# Calculator_Sch.net
KiCad netlist of a schematic drawn in Altium Designer
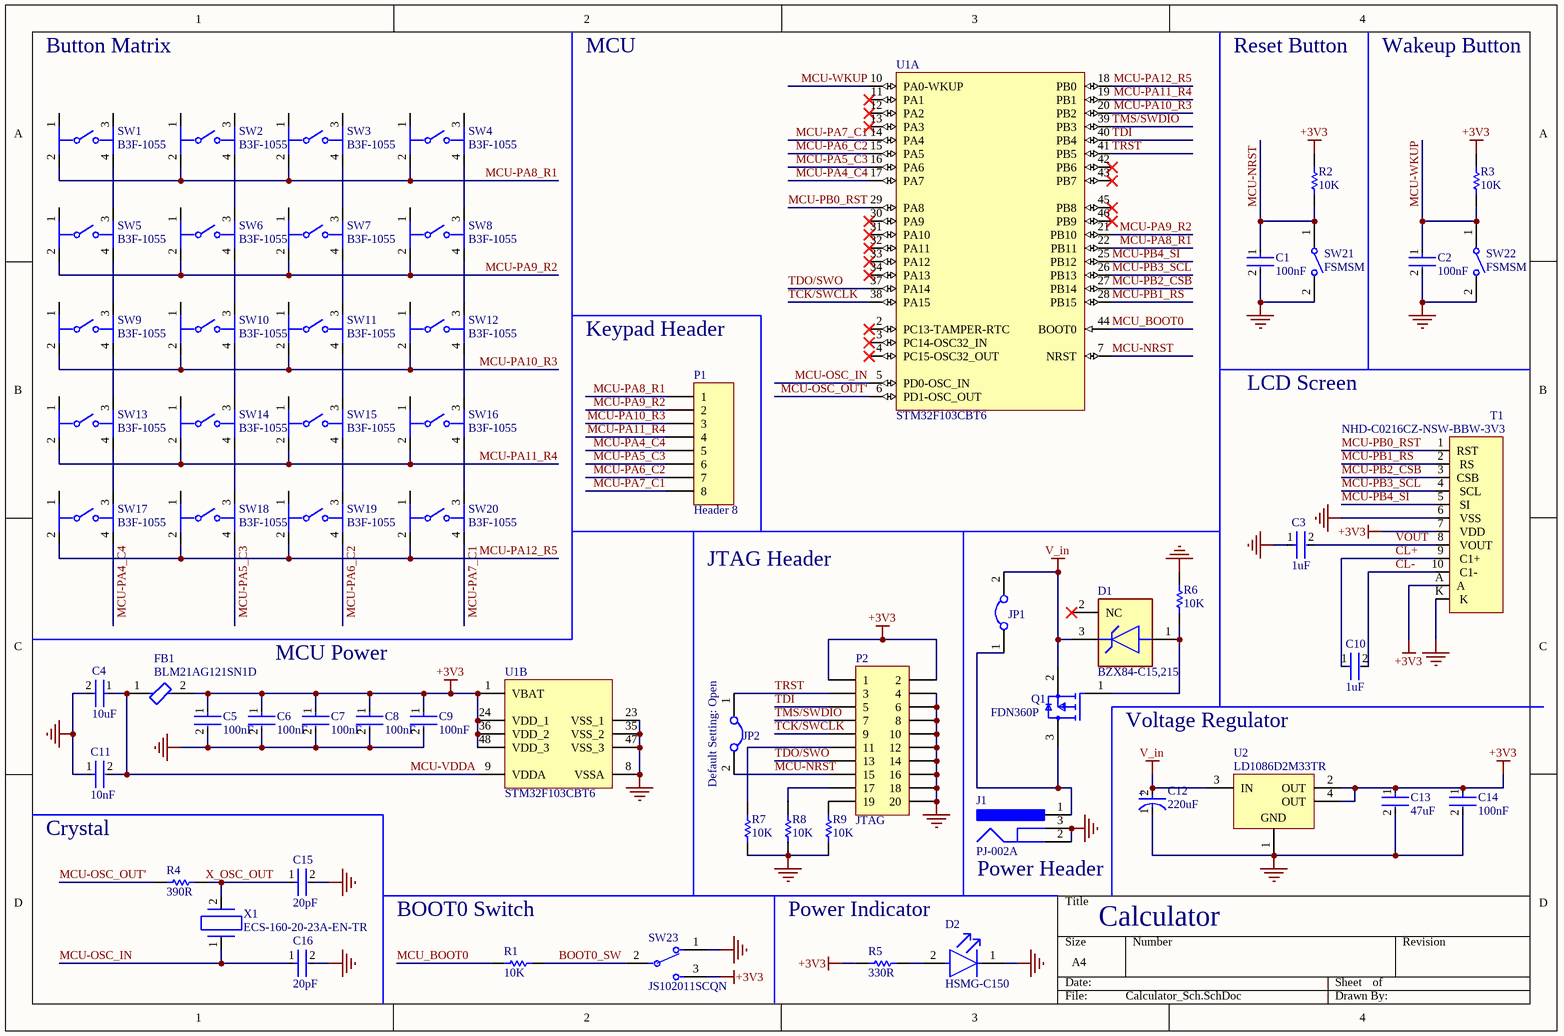
[diagram p0: Calculator_Sch.SchDoc]

(export (version "E")
  (design (tool "Eeschema 10.0.6"))
  (components
    (comp (ref "C1")
      (value "100nF")
      (footprint "FP-C1206C-EB-MFG")
      (description "CAP CER 0.1UF 16V 10% X7R 1206")
      (fields (field (name "MANUFACTURER PART NUMBER") "C1206C104K4RACTU") (field (name "TOLERANCE") "0.1"))
      (libsource (lib "Altium Content Vault") (part "b4654b650e69147ec39a6b967a45e02"))
    )
    (comp (ref "C2")
      (value "100nF")
      (footprint "FP-C1206C-EB-MFG")
      (description "CAP CER 0.1UF 16V 10% X7R 1206")
      (fields (field (name "MANUFACTURER PART NUMBER") "C1206C104K4RACTU") (field (name "TOLERANCE") "0.1"))
      (libsource (lib "Altium Content Vault") (part "b4654b650e69147ec39a6b967a45e02"))
    )
    (comp (ref "C3")
      (value "1uF")
      (footprint "FP-1206-L_3_2_0_2-W_1_6_0-IPC_C")
      (description "General Purpose Ceramic Capacitor, 1206, 1uF, 20%, X7R, 15%, 16V")
      (fields (field (name "TOLERANCE") "20%"))
      (libsource (lib "Altium Content Vault") (part "b4654b650e69147ec39a6b967a45e02"))
    )
    (comp (ref "C4")
      (value "10uF")
      (footprint "FP-1206-L_3_2_0_2-W_1_6_0-IPC_B")
      (description "General Purpose Ceramic Capacitor, 1206, 10uF, 10%, X5R, 15%, 16V")
      (fields (field (name "TOLERANCE") "10%") (field (name "VOLTAGE") "16V"))
      (libsource (lib "Altium Content Vault") (part "02cd4be3c70576c341d710602a673aa"))
    )
    (comp (ref "C5")
      (value "100nF")
      (footprint "FP-C1206C-EB-MFG")
      (description "CAP CER 0.1UF 16V 10% X7R 1206")
      (fields (field (name "MANUFACTURER PART NUMBER") "C1206C104K4RACTU") (field (name "TOLERANCE") "0.1"))
      (libsource (lib "Altium Content Vault") (part "b4654b650e69147ec39a6b967a45e02"))
    )
    (comp (ref "C6")
      (value "100nF")
      (footprint "FP-C1206C-EB-MFG")
      (description "CAP CER 0.1UF 16V 10% X7R 1206")
      (fields (field (name "MANUFACTURER PART NUMBER") "C1206C104K4RACTU") (field (name "TOLERANCE") "0.1"))
      (libsource (lib "Altium Content Vault") (part "b4654b650e69147ec39a6b967a45e02"))
    )
    (comp (ref "C7")
      (value "100nF")
      (footprint "FP-C1206C-EB-MFG")
      (description "CAP CER 0.1UF 16V 10% X7R 1206")
      (fields (field (name "MANUFACTURER PART NUMBER") "C1206C104K4RACTU") (field (name "TOLERANCE") "0.1"))
      (libsource (lib "Altium Content Vault") (part "b4654b650e69147ec39a6b967a45e02"))
    )
    (comp (ref "C8")
      (value "100nF")
      (footprint "FP-C1206C-EB-MFG")
      (description "CAP CER 0.1UF 16V 10% X7R 1206")
      (fields (field (name "MANUFACTURER PART NUMBER") "C1206C104K4RACTU") (field (name "TOLERANCE") "0.1"))
      (libsource (lib "Altium Content Vault") (part "b4654b650e69147ec39a6b967a45e02"))
    )
    (comp (ref "C9")
      (value "100nF")
      (footprint "FP-C1206C-EB-MFG")
      (description "CAP CER 0.1UF 16V 10% X7R 1206")
      (fields (field (name "MANUFACTURER PART NUMBER") "C1206C104K4RACTU") (field (name "TOLERANCE") "0.1"))
      (libsource (lib "Altium Content Vault") (part "b4654b650e69147ec39a6b967a45e02"))
    )
    (comp (ref "C10")
      (value "1uF")
      (footprint "FP-1206-L_3_2_0_2-W_1_6_0-IPC_C")
      (description "General Purpose Ceramic Capacitor, 1206, 1uF, 20%, X7R, 15%, 16V")
      (fields (field (name "TOLERANCE") "20%"))
      (libsource (lib "Altium Content Vault") (part "b4654b650e69147ec39a6b967a45e02"))
    )
    (comp (ref "C11")
      (value "10nF")
      (footprint "FP-C1206C-EB-MFG")
      (description "CAP CER 10000PF 200V X7R 1206")
      (fields
        (field (name "OCTOPART") "https://octopart.com/c1206c103k2ractu-kemet-2299149")
        (field (name "MANUFACTURER") "KEMET")
      )
      (libsource (lib "Altium Content Vault") (part "b4654b650e69147ec39a6b967a45e02"))
    )
    (comp (ref "C12")
      (value "220uF")
      (footprint "FP-TAJE-MFG")
      (description "220uF 16V  ±20% 500mΩ 2917  SMD Tantalum Capacitor")
      (fields (field (name "TOLERANCE") "20%"))
      (libsource (lib "Altium Content Vault") (part "203bc49f2ac43e59fd269a8c329ed05"))
    )
    (comp (ref "C13")
      (value "47uF")
      (footprint "FP-C3216-160-0_2-MFG")
      (description "Multilayer Ceramic Capacitors 47uF ±20% 16V X5R SMD 1206")
      (fields (field (name "TOLERANCE") "20%"))
      (libsource (lib "Altium Content Vault") (part "11868f565c42a9108669ba33697ecf6"))
    )
    (comp (ref "C14")
      (value "100nF")
      (footprint "FP-C1206C-EB-MFG")
      (description "CAP CER 0.1UF 16V 10% X7R 1206")
      (fields (field (name "MANUFACTURER PART NUMBER") "C1206C104K4RACTU") (field (name "TOLERANCE") "0.1"))
      (libsource (lib "Altium Content Vault") (part "b4654b650e69147ec39a6b967a45e02"))
    )
    (comp (ref "C15")
      (value "20pF")
      (footprint "FP-C1206C-EB-MFG")
      (description "1206 C 20pF Ceramic Multilayer Capacitor; 50 VDC; +125degC; C0G Dielec; +/-5%")
      (fields (field (name "TOLERANCE") "0.05") (field (name "MANUFACTURER") "KEMET"))
      (libsource (lib "Altium Content Vault") (part "b4654b650e69147ec39a6b967a45e02"))
    )
    (comp (ref "C16")
      (value "20pF")
      (footprint "FP-C1206C-EB-MFG")
      (description "1206 C 20pF Ceramic Multilayer Capacitor; 50 VDC; +125degC; C0G Dielec; +/-5%")
      (fields (field (name "TOLERANCE") "0.05") (field (name "MANUFACTURER") "KEMET"))
      (libsource (lib "Altium Content Vault") (part "b4654b650e69147ec39a6b967a45e02"))
    )
    (comp (ref "D1")
      (value "BZX84-C15,215")
      (footprint "FP-SOT23-IPC_C")
      (description "DIODE ZENER 15V 250MW TO236AB")
      (libsource (lib "Altium Content Vault") (part "42c7eef1d4f2b235b8dd031160b28fd"))
    )
    (comp (ref "D2")
      (value "HSMG-C150")
      (footprint "FP-HSMG-C150-MFG")
      (description "Surface Mount Chip LEDs")
      (fields (field (name "MANUFACTURER") "Broadcom"))
      (libsource (lib "Altium Content Vault") (part "8706943c75ba83719d021d2fdc84c58"))
    )
    (comp (ref "FB1")
      (value "BLM21AG121SN1D")
      (footprint "FP-BLM21-0_2-t0_85-e0_5-IPC_A")
      (description "FERRITE BEAD 120 OHM 0805 1LN")
      (fields (field (name "TOLERANCE") "25%"))
      (libsource (lib "Altium Content Vault") (part "5f30dd21d616792df468990f7003faa"))
    )
    (comp (ref "J1")
      (value "PJ-002A")
      (footprint "CUI-PJ-002A_V")
      (fields (field (name "MANUFACTURER") "CUIInc."))
      (libsource (lib "Altium Content Vault") (part "JACK-2CD3-RN_B"))
    )
    (comp (ref "JP1")
      (value "Jumper")
      (footprint "Jumper Small - 2.54 - GRAY")
      (libsource (lib "My Library") (part "Jumper"))
    )
    (comp (ref "JP2")
      (value "Jumper")
      (footprint "Jumper Small - 2.54 - GRAY")
      (libsource (lib "My Library") (part "Jumper"))
    )
    (comp (ref "P1")
      (value "Header 8")
      (footprint "HDR1X8")
      (description "Header, 8-Pin")
      (fields (field (name "PUBLISHER") "Altium Limited"))
      (libsource (lib "Miscellaneous Connectors") (part "Header 8"))
    )
    (comp (ref "P2")
      (value "JTAG")
      (footprint "HDR2X10")
      (description "Header, 10-Pin, Dual row")
      (fields (field (name "PUBLISHER") "Altium Limited"))
      (libsource (lib "Miscellaneous Connectors") (part "Header 10X2"))
    )
    (comp (ref "Q1")
      (value "FDN360P")
      (footprint "FP-527AG-IPC_B")
      (description "MOSFET P-CH 30V 2A SSOT3")
      (libsource (lib "Altium Content Vault") (part "d96140c8e79ef71348df71fb49a9466"))
    )
    (comp (ref "R1")
      (value "10K")
      (footprint "RESC3116X65X40ML10T20")
      (description "Chip Resistor, 10 KOhm, +/- 1%, 0.25 W, -55 to 155 degC, 1206 (3216 Metric), RoHS, Tape and Reel")
      (fields (field (name "TOLERANCE") "1%") (field (name "MANUFACTURER") "Yageo"))
      (libsource (lib "Altium Content Vault") (part "RES-2"))
    )
    (comp (ref "R2")
      (value "10K")
      (footprint "RESC3116X65X40ML10T20")
      (description "Chip Resistor, 10 KOhm, +/- 1%, 0.25 W, -55 to 155 degC, 1206 (3216 Metric), RoHS, Tape and Reel")
      (fields (field (name "TOLERANCE") "1%") (field (name "MANUFACTURER") "Yageo"))
      (libsource (lib "Altium Content Vault") (part "RES-2"))
    )
    (comp (ref "R3")
      (value "10K")
      (footprint "RESC3116X65X40ML10T20")
      (description "Chip Resistor, 10 KOhm, +/- 1%, 0.25 W, -55 to 155 degC, 1206 (3216 Metric), RoHS, Tape and Reel")
      (fields (field (name "TOLERANCE") "1%") (field (name "MANUFACTURER") "Yageo"))
      (libsource (lib "Altium Content Vault") (part "RES-2"))
    )
    (comp (ref "R4")
      (value "390R")
      (footprint "RESC3216X60X45NL10T20")
      (fields (field (name "MANUFACTURER") "Vishay Dale") (field (name "PART NUMBER") "CRCW1206390RJNEA"))
      (libsource (lib "Altium Content Vault") (part "RES"))
    )
    (comp (ref "R5")
      (value "330R")
      (footprint "RESC3116X65X40LL10T20")
      (description "Chip Resistor, 330 Ohm, +/- 1%, 250 mW, -55 to 155 degC, 1206 (3216 Metric), RoHS, Tape and Reel")
      (fields (field (name "MANUFACTURER") "Yageo") (field (name "TOLERANCE") "1%"))
      (libsource (lib "Altium Content Vault") (part "RES-2"))
    )
    (comp (ref "R6")
      (value "10K")
      (footprint "RESC3116X65X40ML10T20")
      (description "Chip Resistor, 10 KOhm, +/- 1%, 0.25 W, -55 to 155 degC, 1206 (3216 Metric), RoHS, Tape and Reel")
      (fields (field (name "TOLERANCE") "1%") (field (name "MANUFACTURER") "Yageo"))
      (libsource (lib "Altium Content Vault") (part "RES-2"))
    )
    (comp (ref "R7")
      (value "10K")
      (footprint "RESC3116X65X40ML10T20")
      (description "Chip Resistor, 10 KOhm, +/- 1%, 0.25 W, -55 to 155 degC, 1206 (3216 Metric), RoHS, Tape and Reel")
      (fields (field (name "TOLERANCE") "1%") (field (name "MANUFACTURER") "Yageo"))
      (libsource (lib "Altium Content Vault") (part "RES-2"))
    )
    (comp (ref "R8")
      (value "10K")
      (footprint "RESC3116X65X40ML10T20")
      (description "Chip Resistor, 10 KOhm, +/- 1%, 0.25 W, -55 to 155 degC, 1206 (3216 Metric), RoHS, Tape and Reel")
      (fields (field (name "TOLERANCE") "1%") (field (name "MANUFACTURER") "Yageo"))
      (libsource (lib "Altium Content Vault") (part "RES-2"))
    )
    (comp (ref "R9")
      (value "10K")
      (footprint "RESC3116X65X40ML10T20")
      (description "Chip Resistor, 10 KOhm, +/- 1%, 0.25 W, -55 to 155 degC, 1206 (3216 Metric), RoHS, Tape and Reel")
      (fields (field (name "TOLERANCE") "1%") (field (name "MANUFACTURER") "Yageo"))
      (libsource (lib "Altium Content Vault") (part "RES-2"))
    )
    (comp (ref "SW1")
      (value "B3F-1055")
      (footprint "FP-B3F-1055-MFG")
      (description "SWITCH TACTILE SPST-NO 0.05A 24V")
      (libsource (lib "Altium Content Vault") (part "b8895f3f4cefb76e1819d2863dba89b"))
    )
    (comp (ref "SW2")
      (value "B3F-1055")
      (footprint "FP-B3F-1055-MFG")
      (description "SWITCH TACTILE SPST-NO 0.05A 24V")
      (libsource (lib "Altium Content Vault") (part "b8895f3f4cefb76e1819d2863dba89b"))
    )
    (comp (ref "SW3")
      (value "B3F-1055")
      (footprint "FP-B3F-1055-MFG")
      (description "SWITCH TACTILE SPST-NO 0.05A 24V")
      (libsource (lib "Altium Content Vault") (part "b8895f3f4cefb76e1819d2863dba89b"))
    )
    (comp (ref "SW4")
      (value "B3F-1055")
      (footprint "FP-B3F-1055-MFG")
      (description "SWITCH TACTILE SPST-NO 0.05A 24V")
      (libsource (lib "Altium Content Vault") (part "b8895f3f4cefb76e1819d2863dba89b"))
    )
    (comp (ref "SW5")
      (value "B3F-1055")
      (footprint "FP-B3F-1055-MFG")
      (description "SWITCH TACTILE SPST-NO 0.05A 24V")
      (libsource (lib "Altium Content Vault") (part "b8895f3f4cefb76e1819d2863dba89b"))
    )
    (comp (ref "SW6")
      (value "B3F-1055")
      (footprint "FP-B3F-1055-MFG")
      (description "SWITCH TACTILE SPST-NO 0.05A 24V")
      (libsource (lib "Altium Content Vault") (part "b8895f3f4cefb76e1819d2863dba89b"))
    )
    (comp (ref "SW7")
      (value "B3F-1055")
      (footprint "FP-B3F-1055-MFG")
      (description "SWITCH TACTILE SPST-NO 0.05A 24V")
      (libsource (lib "Altium Content Vault") (part "b8895f3f4cefb76e1819d2863dba89b"))
    )
    (comp (ref "SW8")
      (value "B3F-1055")
      (footprint "FP-B3F-1055-MFG")
      (description "SWITCH TACTILE SPST-NO 0.05A 24V")
      (libsource (lib "Altium Content Vault") (part "b8895f3f4cefb76e1819d2863dba89b"))
    )
    (comp (ref "SW9")
      (value "B3F-1055")
      (footprint "FP-B3F-1055-MFG")
      (description "SWITCH TACTILE SPST-NO 0.05A 24V")
      (libsource (lib "Altium Content Vault") (part "b8895f3f4cefb76e1819d2863dba89b"))
    )
    (comp (ref "SW10")
      (value "B3F-1055")
      (footprint "FP-B3F-1055-MFG")
      (description "SWITCH TACTILE SPST-NO 0.05A 24V")
      (libsource (lib "Altium Content Vault") (part "b8895f3f4cefb76e1819d2863dba89b"))
    )
    (comp (ref "SW11")
      (value "B3F-1055")
      (footprint "FP-B3F-1055-MFG")
      (description "SWITCH TACTILE SPST-NO 0.05A 24V")
      (libsource (lib "Altium Content Vault") (part "b8895f3f4cefb76e1819d2863dba89b"))
    )
    (comp (ref "SW12")
      (value "B3F-1055")
      (footprint "FP-B3F-1055-MFG")
      (description "SWITCH TACTILE SPST-NO 0.05A 24V")
      (libsource (lib "Altium Content Vault") (part "b8895f3f4cefb76e1819d2863dba89b"))
    )
    (comp (ref "SW13")
      (value "B3F-1055")
      (footprint "FP-B3F-1055-MFG")
      (description "SWITCH TACTILE SPST-NO 0.05A 24V")
      (libsource (lib "Altium Content Vault") (part "b8895f3f4cefb76e1819d2863dba89b"))
    )
    (comp (ref "SW14")
      (value "B3F-1055")
      (footprint "FP-B3F-1055-MFG")
      (description "SWITCH TACTILE SPST-NO 0.05A 24V")
      (libsource (lib "Altium Content Vault") (part "b8895f3f4cefb76e1819d2863dba89b"))
    )
    (comp (ref "SW15")
      (value "B3F-1055")
      (footprint "FP-B3F-1055-MFG")
      (description "SWITCH TACTILE SPST-NO 0.05A 24V")
      (libsource (lib "Altium Content Vault") (part "b8895f3f4cefb76e1819d2863dba89b"))
    )
    (comp (ref "SW16")
      (value "B3F-1055")
      (footprint "FP-B3F-1055-MFG")
      (description "SWITCH TACTILE SPST-NO 0.05A 24V")
      (libsource (lib "Altium Content Vault") (part "b8895f3f4cefb76e1819d2863dba89b"))
    )
    (comp (ref "SW17")
      (value "B3F-1055")
      (footprint "FP-B3F-1055-MFG")
      (description "SWITCH TACTILE SPST-NO 0.05A 24V")
      (libsource (lib "Altium Content Vault") (part "b8895f3f4cefb76e1819d2863dba89b"))
    )
    (comp (ref "SW18")
      (value "B3F-1055")
      (footprint "FP-B3F-1055-MFG")
      (description "SWITCH TACTILE SPST-NO 0.05A 24V")
      (libsource (lib "Altium Content Vault") (part "b8895f3f4cefb76e1819d2863dba89b"))
    )
    (comp (ref "SW19")
      (value "B3F-1055")
      (footprint "FP-B3F-1055-MFG")
      (description "SWITCH TACTILE SPST-NO 0.05A 24V")
      (libsource (lib "Altium Content Vault") (part "b8895f3f4cefb76e1819d2863dba89b"))
    )
    (comp (ref "SW20")
      (value "B3F-1055")
      (footprint "FP-B3F-1055-MFG")
      (description "SWITCH TACTILE SPST-NO 0.05A 24V")
      (libsource (lib "Altium Content Vault") (part "b8895f3f4cefb76e1819d2863dba89b"))
    )
    (comp (ref "SW21")
      (value "FSMSM")
      (footprint "TECO-FSMSM-2_V")
      (description "FSMSM Push Button Switch, 50 mA, -35 to 85 degC, 2-Pin SMD, RoHS, Bulk")
      (fields (field (name "MANUFACTURER") "TE Connectivity"))
      (libsource (lib "Altium Content Vault") (part "SW-SPST-2_C"))
    )
    (comp (ref "SW22")
      (value "FSMSM")
      (footprint "TECO-FSMSM-2_V")
      (description "FSMSM Push Button Switch, 50 mA, -35 to 85 degC, 2-Pin SMD, RoHS, Bulk")
      (fields (field (name "MANUFACTURER") "TE Connectivity"))
      (libsource (lib "Altium Content Vault") (part "SW-SPST-2_C"))
    )
    (comp (ref "SW23")
      (value "JS102011SCQN")
      (footprint "FP-JS102011SCQN-MFG")
      (description "SWITCH SLIDE SPDT 300MA 6V")
      (libsource (lib "Altium Content Vault") (part "39e195cbbadc85d1df0d7eb6847d379"))
    )
    (comp (ref "T1")
      (value "NHD-C0216CZ-NSW-BBW-3V3")
      (footprint "NHD-C0216CZ-NSW-BBW-3V3")
      (description "LCD MOD 32DIG 16X2 TRANSMISV WHT")
      (libsource (lib "Calculator_SchLib") (part "NHD-C0216CZ-NSW-BBW-3V3"))
    )
    (comp (ref "U1")
      (value "STM32F103CBT6")
      (footprint "STM-LQFP48_L")
      (libsource (lib "Altium Content Vault") (part "MC-ARM-STM32F103X8_B-SQ48"))
    )
    (comp (ref "U2")
      (value "LD1086D2M33TR")
      (footprint "D2PAK_A_L")
      (description "1.5A, Low Drop Positive Voltage Regulator, 3.3V, 4-Pin D2PAK/A, Tape and Reel")
      (libsource (lib "Altium Content Vault") (part "PM-REG-LD1085-SOT4"))
    )
    (comp (ref "X1")
      (value "ECS-160-20-23A-EN-TR")
      (footprint "ECX-64AEN/64CEN")
      (description "CRYSTAL 16.0000MHZ 20PF SMD")
      (libsource (lib "Calculator_SchLib") (part "ECS-160-20-23A-EN-TR"))
    )
  )
  (nets
    (net (code "1") (name "+3V3") (class "Default")
      (node (ref "C13") (pin "1") (pinfunction "1_1") (pintype "passive"))
      (node (ref "C14") (pin "1") (pinfunction "1_1") (pintype "passive"))
      (node (ref "C5") (pin "1") (pinfunction "1_1") (pintype "passive"))
      (node (ref "C6") (pin "1") (pinfunction "1_1") (pintype "passive"))
      (node (ref "C7") (pin "1") (pinfunction "1_1") (pintype "passive"))
      (node (ref "C8") (pin "1") (pinfunction "1_1") (pintype "passive"))
      (node (ref "C9") (pin "1") (pinfunction "1_1") (pintype "passive"))
      (node (ref "FB1") (pin "2") (pinfunction "2_2") (pintype "passive"))
      (node (ref "P2") (pin "1") (pinfunction "1_1") (pintype "passive"))
      (node (ref "P2") (pin "2") (pinfunction "2_2") (pintype "passive"))
      (node (ref "R2") (pin "2") (pinfunction "2_2") (pintype "passive"))
      (node (ref "R3") (pin "2") (pinfunction "2_2") (pintype "passive"))
      (node (ref "R5") (pin "1") (pinfunction "1_1") (pintype "passive"))
      (node (ref "SW23") (pin "3") (pinfunction "3_3") (pintype "passive"))
      (node (ref "T1") (pin "7") (pinfunction "_VDD_7") (pintype "passive"))
      (node (ref "T1") (pin "A") (pinfunction "A_A") (pintype "passive"))
      (node (ref "U1") (pin "1") (pinfunction "VBAT_1") (pintype "power_in"))
      (node (ref "U1") (pin "24") (pinfunction "VDD_1_24") (pintype "power_in"))
      (node (ref "U1") (pin "36") (pinfunction "VDD_2_36") (pintype "power_in"))
      (node (ref "U1") (pin "48") (pinfunction "VDD_3_48") (pintype "power_in"))
      (node (ref "U2") (pin "2") (pinfunction "OUT_2") (pintype "power_in"))
      (node (ref "U2") (pin "4") (pinfunction "OUT_4") (pintype "power_in"))
    )
    (net (code "2") (name "/BOOT0_SW") (class "Default")
      (node (ref "R1") (pin "2") (pinfunction "2_2") (pintype "passive"))
      (node (ref "SW23") (pin "2") (pinfunction "C_2") (pintype "passive"))
    )
    (net (code "3") (name "/CL+") (class "Default")
      (node (ref "C10") (pin "1") (pinfunction "1_1") (pintype "passive"))
      (node (ref "T1") (pin "9") (pinfunction "_C1+_9") (pintype "passive"))
    )
    (net (code "4") (name "/CL-") (class "Default")
      (node (ref "C10") (pin "2") (pinfunction "2_2") (pintype "passive"))
      (node (ref "T1") (pin "10") (pinfunction "_C1-_10") (pintype "passive"))
    )
    (net (code "5") (name "/MCU-NRST") (class "Default")
      (node (ref "C1") (pin "1") (pinfunction "1_1") (pintype "passive"))
      (node (ref "JP2") (pin "2") (pinfunction "2_2") (pintype "passive"))
      (node (ref "P2") (pin "15") (pinfunction "15_15") (pintype "passive"))
      (node (ref "R2") (pin "1") (pinfunction "1_1") (pintype "passive"))
      (node (ref "SW21") (pin "1") (pinfunction "1_1") (pintype "passive"))
      (node (ref "U1") (pin "7") (pinfunction "NRST_7") (pintype "bidirectional"))
    )
    (net (code "6") (name "/MCU-OSC_IN") (class "Default")
      (node (ref "C16") (pin "1") (pinfunction "1_1") (pintype "passive"))
      (node (ref "U1") (pin "5") (pinfunction "PD0-OSC_IN_5") (pintype "bidirectional"))
      (node (ref "X1") (pin "1") (pinfunction "1_1") (pintype "passive"))
    )
    (net (code "7") (name "/MCU-OSC_OUT'") (class "Default")
      (node (ref "R4") (pin "1") (pinfunction "1_1") (pintype "passive"))
      (node (ref "U1") (pin "6") (pinfunction "PD1-OSC_OUT_6") (pintype "bidirectional"))
    )
    (net (code "8") (name "/MCU-PA4_C4") (class "Default")
      (node (ref "P1") (pin "5") (pinfunction "5_5") (pintype "passive"))
      (node (ref "SW17") (pin "4") (pinfunction "4_4") (pintype "passive"))
      (node (ref "U1") (pin "17") (pinfunction "PA7_17") (pintype "bidirectional"))
    )
    (net (code "9") (name "/MCU-PA5_C3") (class "Default")
      (node (ref "P1") (pin "6") (pinfunction "6_6") (pintype "passive"))
      (node (ref "SW18") (pin "4") (pinfunction "4_4") (pintype "passive"))
      (node (ref "U1") (pin "16") (pinfunction "PA6_16") (pintype "bidirectional"))
    )
    (net (code "10") (name "/MCU-PA6_C2") (class "Default")
      (node (ref "P1") (pin "7") (pinfunction "7_7") (pintype "passive"))
      (node (ref "SW19") (pin "4") (pinfunction "4_4") (pintype "passive"))
      (node (ref "U1") (pin "15") (pinfunction "PA5_15") (pintype "bidirectional"))
    )
    (net (code "11") (name "/MCU-PA7_C1") (class "Default")
      (node (ref "P1") (pin "8") (pinfunction "8_8") (pintype "passive"))
      (node (ref "SW20") (pin "4") (pinfunction "4_4") (pintype "passive"))
      (node (ref "U1") (pin "14") (pinfunction "PA4_14") (pintype "bidirectional"))
    )
    (net (code "12") (name "/MCU-PA8_R1") (class "Default")
      (node (ref "P1") (pin "1") (pinfunction "1_1") (pintype "passive"))
      (node (ref "SW1") (pin "2") (pinfunction "2_2") (pintype "passive"))
      (node (ref "SW2") (pin "2") (pinfunction "2_2") (pintype "passive"))
      (node (ref "SW3") (pin "2") (pinfunction "2_2") (pintype "passive"))
      (node (ref "SW4") (pin "2") (pinfunction "2_2") (pintype "passive"))
      (node (ref "U1") (pin "22") (pinfunction "PB11_22") (pintype "bidirectional"))
    )
    (net (code "13") (name "/MCU-PA9_R2") (class "Default")
      (node (ref "P1") (pin "2") (pinfunction "2_2") (pintype "passive"))
      (node (ref "SW5") (pin "2") (pinfunction "2_2") (pintype "passive"))
      (node (ref "SW6") (pin "2") (pinfunction "2_2") (pintype "passive"))
      (node (ref "SW7") (pin "2") (pinfunction "2_2") (pintype "passive"))
      (node (ref "SW8") (pin "2") (pinfunction "2_2") (pintype "passive"))
      (node (ref "U1") (pin "21") (pinfunction "PB10_21") (pintype "bidirectional"))
    )
    (net (code "14") (name "/MCU-PA10_R3") (class "Default")
      (node (ref "P1") (pin "3") (pinfunction "3_3") (pintype "passive"))
      (node (ref "SW10") (pin "2") (pinfunction "2_2") (pintype "passive"))
      (node (ref "SW11") (pin "2") (pinfunction "2_2") (pintype "passive"))
      (node (ref "SW12") (pin "2") (pinfunction "2_2") (pintype "passive"))
      (node (ref "SW9") (pin "2") (pinfunction "2_2") (pintype "passive"))
      (node (ref "U1") (pin "20") (pinfunction "PB2_20") (pintype "bidirectional"))
    )
    (net (code "15") (name "/MCU-PA11_R4") (class "Default")
      (node (ref "P1") (pin "4") (pinfunction "4_4") (pintype "passive"))
      (node (ref "SW13") (pin "2") (pinfunction "2_2") (pintype "passive"))
      (node (ref "SW14") (pin "2") (pinfunction "2_2") (pintype "passive"))
      (node (ref "SW15") (pin "2") (pinfunction "2_2") (pintype "passive"))
      (node (ref "SW16") (pin "2") (pinfunction "2_2") (pintype "passive"))
      (node (ref "U1") (pin "19") (pinfunction "PB1_19") (pintype "bidirectional"))
    )
    (net (code "16") (name "/MCU-PA12_R5") (class "Default")
      (node (ref "SW17") (pin "2") (pinfunction "2_2") (pintype "passive"))
      (node (ref "SW18") (pin "2") (pinfunction "2_2") (pintype "passive"))
      (node (ref "SW19") (pin "2") (pinfunction "2_2") (pintype "passive"))
      (node (ref "SW20") (pin "2") (pinfunction "2_2") (pintype "passive"))
      (node (ref "U1") (pin "18") (pinfunction "PB0_18") (pintype "bidirectional"))
    )
    (net (code "17") (name "/MCU-PB0_RST") (class "Default")
      (node (ref "T1") (pin "1") (pinfunction "RST_1") (pintype "passive"))
      (node (ref "U1") (pin "29") (pinfunction "PA8_29") (pintype "bidirectional"))
    )
    (net (code "18") (name "/MCU-PB1_RS") (class "Default")
      (node (ref "T1") (pin "2") (pinfunction "_RS_2") (pintype "passive"))
      (node (ref "U1") (pin "28") (pinfunction "PB15_28") (pintype "bidirectional"))
    )
    (net (code "19") (name "/MCU-PB2_CSB") (class "Default")
      (node (ref "T1") (pin "3") (pinfunction "CSB_3") (pintype "passive"))
      (node (ref "U1") (pin "27") (pinfunction "PB14_27") (pintype "bidirectional"))
    )
    (net (code "20") (name "/MCU-PB3_SCL") (class "Default")
      (node (ref "T1") (pin "4") (pinfunction "_SCL_4") (pintype "passive"))
      (node (ref "U1") (pin "26") (pinfunction "PB13_26") (pintype "bidirectional"))
    )
    (net (code "21") (name "/MCU-PB4_SI") (class "Default")
      (node (ref "T1") (pin "5") (pinfunction "_SI_5") (pintype "passive"))
      (node (ref "U1") (pin "25") (pinfunction "PB12_25") (pintype "bidirectional"))
    )
    (net (code "22") (name "/MCU-VDDA") (class "Default")
      (node (ref "C11") (pin "2") (pinfunction "2_2") (pintype "passive"))
      (node (ref "C4") (pin "1") (pinfunction "1_1") (pintype "passive"))
      (node (ref "FB1") (pin "1") (pinfunction "1_1") (pintype "passive"))
      (node (ref "U1") (pin "9") (pinfunction "VDDA_9") (pintype "power_in"))
    )
    (net (code "23") (name "/MCU-WKUP") (class "Default")
      (node (ref "C2") (pin "1") (pinfunction "1_1") (pintype "passive"))
      (node (ref "R3") (pin "1") (pinfunction "1_1") (pintype "passive"))
      (node (ref "SW22") (pin "1") (pinfunction "1_1") (pintype "passive"))
      (node (ref "U1") (pin "10") (pinfunction "PA0-WKUP_10") (pintype "bidirectional"))
    )
    (net (code "24") (name "/MCU_BOOT0") (class "Default")
      (node (ref "R1") (pin "1") (pinfunction "1_1") (pintype "passive"))
      (node (ref "U1") (pin "44") (pinfunction "BOOT0_44") (pintype "input"))
    )
    (net (code "25") (name "/TCK{slash}SWCLK") (class "Default")
      (node (ref "P2") (pin "9") (pinfunction "9_9") (pintype "passive"))
      (node (ref "U1") (pin "38") (pinfunction "PA15_38") (pintype "bidirectional"))
    )
    (net (code "26") (name "/TDI") (class "Default")
      (node (ref "P2") (pin "5") (pinfunction "5_5") (pintype "passive"))
      (node (ref "U1") (pin "40") (pinfunction "PB4_40") (pintype "bidirectional"))
    )
    (net (code "27") (name "/TDO{slash}SWO") (class "Default")
      (node (ref "P2") (pin "13") (pinfunction "13_13") (pintype "passive"))
      (node (ref "U1") (pin "37") (pinfunction "PA14_37") (pintype "bidirectional"))
    )
    (net (code "28") (name "/TMS{slash}SWDIO") (class "Default")
      (node (ref "P2") (pin "7") (pinfunction "7_7") (pintype "passive"))
      (node (ref "U1") (pin "39") (pinfunction "PB3_39") (pintype "bidirectional"))
    )
    (net (code "29") (name "/TRST") (class "Default")
      (node (ref "JP2") (pin "1") (pinfunction "1_1") (pintype "passive"))
      (node (ref "P2") (pin "3") (pinfunction "3_3") (pintype "passive"))
      (node (ref "U1") (pin "41") (pinfunction "PB5_41") (pintype "bidirectional"))
    )
    (net (code "30") (name "/VOUT") (class "Default")
      (node (ref "C3") (pin "2") (pinfunction "2_2") (pintype "passive"))
      (node (ref "T1") (pin "8") (pinfunction "_VOUT_8") (pintype "passive"))
    )
    (net (code "31") (name "/X_OSC_OUT") (class "Default")
      (node (ref "C15") (pin "1") (pinfunction "1_1") (pintype "passive"))
      (node (ref "R4") (pin "2") (pinfunction "2_2") (pintype "passive"))
      (node (ref "X1") (pin "2") (pinfunction "2_2") (pintype "passive"))
    )
    (net (code "32") (name "GND") (class "Default")
      (node (ref "C1") (pin "2") (pinfunction "2_2") (pintype "passive"))
      (node (ref "C11") (pin "1") (pinfunction "1_1") (pintype "passive"))
      (node (ref "C12") (pin "1") (pinfunction "C_1") (pintype "passive"))
      (node (ref "C13") (pin "2") (pinfunction "2_2") (pintype "passive"))
      (node (ref "C14") (pin "2") (pinfunction "2_2") (pintype "passive"))
      (node (ref "C15") (pin "2") (pinfunction "2_2") (pintype "passive"))
      (node (ref "C16") (pin "2") (pinfunction "2_2") (pintype "passive"))
      (node (ref "C2") (pin "2") (pinfunction "2_2") (pintype "passive"))
      (node (ref "C3") (pin "1") (pinfunction "1_1") (pintype "passive"))
      (node (ref "C4") (pin "2") (pinfunction "2_2") (pintype "passive"))
      (node (ref "C5") (pin "2") (pinfunction "2_2") (pintype "passive"))
      (node (ref "C6") (pin "2") (pinfunction "2_2") (pintype "passive"))
      (node (ref "C7") (pin "2") (pinfunction "2_2") (pintype "passive"))
      (node (ref "C8") (pin "2") (pinfunction "2_2") (pintype "passive"))
      (node (ref "C9") (pin "2") (pinfunction "2_2") (pintype "passive"))
      (node (ref "D2") (pin "1") (pinfunction "C_1") (pintype "passive"))
      (node (ref "J1") (pin "2") (pinfunction "2_2") (pintype "passive"))
      (node (ref "J1") (pin "3") (pinfunction "3_3") (pintype "passive"))
      (node (ref "P2") (pin "10") (pinfunction "10_10") (pintype "passive"))
      (node (ref "P2") (pin "12") (pinfunction "12_12") (pintype "passive"))
      (node (ref "P2") (pin "14") (pinfunction "14_14") (pintype "passive"))
      (node (ref "P2") (pin "16") (pinfunction "16_16") (pintype "passive"))
      (node (ref "P2") (pin "18") (pinfunction "18_18") (pintype "passive"))
      (node (ref "P2") (pin "20") (pinfunction "20_20") (pintype "passive"))
      (node (ref "P2") (pin "4") (pinfunction "4_4") (pintype "passive"))
      (node (ref "P2") (pin "6") (pinfunction "6_6") (pintype "passive"))
      (node (ref "P2") (pin "8") (pinfunction "8_8") (pintype "passive"))
      (node (ref "R6") (pin "1") (pinfunction "1_1") (pintype "passive"))
      (node (ref "R7") (pin "1") (pinfunction "1_1") (pintype "passive"))
      (node (ref "R8") (pin "1") (pinfunction "1_1") (pintype "passive"))
      (node (ref "R9") (pin "1") (pinfunction "1_1") (pintype "passive"))
      (node (ref "SW21") (pin "2") (pinfunction "2_2") (pintype "passive"))
      (node (ref "SW22") (pin "2") (pinfunction "2_2") (pintype "passive"))
      (node (ref "SW23") (pin "1") (pinfunction "1_1") (pintype "passive"))
      (node (ref "T1") (pin "6") (pinfunction "_VSS_6") (pintype "passive"))
      (node (ref "T1") (pin "K") (pinfunction "_K_K") (pintype "passive"))
      (node (ref "U1") (pin "23") (pinfunction "VSS_1_23") (pintype "power_in"))
      (node (ref "U1") (pin "35") (pinfunction "VSS_2_35") (pintype "power_in"))
      (node (ref "U1") (pin "47") (pinfunction "VSS_3_47") (pintype "power_in"))
      (node (ref "U1") (pin "8") (pinfunction "VSSA_8") (pintype "power_in"))
      (node (ref "U2") (pin "1") (pinfunction "GND_1") (pintype "power_in"))
    )
    (net (code "33") (name "Net-(D1-A)") (class "Default")
      (node (ref "D1") (pin "1") (pinfunction "A_1") (pintype "passive"))
      (node (ref "Q1") (pin "1") (pinfunction "G_1") (pintype "passive"))
      (node (ref "R6") (pin "2") (pinfunction "2_2") (pintype "passive"))
    )
    (net (code "34") (name "Net-(D2-A)") (class "Default")
      (node (ref "D2") (pin "2") (pinfunction "A_2") (pintype "passive"))
      (node (ref "R5") (pin "2") (pinfunction "2_2") (pintype "passive"))
    )
    (net (code "35") (name "Net-(P2-Pad11)") (class "Default")
      (node (ref "P2") (pin "11") (pinfunction "11_11") (pintype "passive"))
      (node (ref "R7") (pin "2") (pinfunction "2_2") (pintype "passive"))
    )
    (net (code "36") (name "Net-(P2-Pad17)") (class "Default")
      (node (ref "P2") (pin "17") (pinfunction "17_17") (pintype "passive"))
      (node (ref "R8") (pin "2") (pinfunction "2_2") (pintype "passive"))
    )
    (net (code "37") (name "Net-(P2-Pad19)") (class "Default")
      (node (ref "P2") (pin "19") (pinfunction "19_19") (pintype "passive"))
      (node (ref "R9") (pin "2") (pinfunction "2_2") (pintype "passive"))
    )
    (net (code "38") (name "Net-(Q1-D)") (class "Default")
      (node (ref "J1") (pin "1") (pinfunction "1_1") (pintype "passive"))
      (node (ref "JP1") (pin "1") (pinfunction "1_1") (pintype "passive"))
      (node (ref "Q1") (pin "3") (pinfunction "D_3") (pintype "passive"))
    )
    (net (code "39") (name "Net-(SW1-Pad4)") (class "Default")
      (node (ref "SW1") (pin "4") (pinfunction "4_4") (pintype "passive"))
      (node (ref "SW5") (pin "3") (pinfunction "3_3") (pintype "passive"))
    )
    (net (code "40") (name "Net-(SW2-Pad4)") (class "Default")
      (node (ref "SW2") (pin "4") (pinfunction "4_4") (pintype "passive"))
      (node (ref "SW6") (pin "3") (pinfunction "3_3") (pintype "passive"))
    )
    (net (code "41") (name "Net-(SW3-Pad4)") (class "Default")
      (node (ref "SW3") (pin "4") (pinfunction "4_4") (pintype "passive"))
      (node (ref "SW7") (pin "3") (pinfunction "3_3") (pintype "passive"))
    )
    (net (code "42") (name "Net-(SW4-Pad4)") (class "Default")
      (node (ref "SW4") (pin "4") (pinfunction "4_4") (pintype "passive"))
      (node (ref "SW8") (pin "3") (pinfunction "3_3") (pintype "passive"))
    )
    (net (code "43") (name "Net-(SW5-Pad4)") (class "Default")
      (node (ref "SW5") (pin "4") (pinfunction "4_4") (pintype "passive"))
      (node (ref "SW9") (pin "3") (pinfunction "3_3") (pintype "passive"))
    )
    (net (code "44") (name "Net-(SW10-Pad3)") (class "Default")
      (node (ref "SW10") (pin "3") (pinfunction "3_3") (pintype "passive"))
      (node (ref "SW6") (pin "4") (pinfunction "4_4") (pintype "passive"))
    )
    (net (code "45") (name "Net-(SW10-Pad4)") (class "Default")
      (node (ref "SW10") (pin "4") (pinfunction "4_4") (pintype "passive"))
      (node (ref "SW14") (pin "3") (pinfunction "3_3") (pintype "passive"))
    )
    (net (code "46") (name "Net-(SW11-Pad3)") (class "Default")
      (node (ref "SW11") (pin "3") (pinfunction "3_3") (pintype "passive"))
      (node (ref "SW7") (pin "4") (pinfunction "4_4") (pintype "passive"))
    )
    (net (code "47") (name "Net-(SW11-Pad4)") (class "Default")
      (node (ref "SW11") (pin "4") (pinfunction "4_4") (pintype "passive"))
      (node (ref "SW15") (pin "3") (pinfunction "3_3") (pintype "passive"))
    )
    (net (code "48") (name "Net-(SW12-Pad3)") (class "Default")
      (node (ref "SW12") (pin "3") (pinfunction "3_3") (pintype "passive"))
      (node (ref "SW8") (pin "4") (pinfunction "4_4") (pintype "passive"))
    )
    (net (code "49") (name "Net-(SW12-Pad4)") (class "Default")
      (node (ref "SW12") (pin "4") (pinfunction "4_4") (pintype "passive"))
      (node (ref "SW16") (pin "3") (pinfunction "3_3") (pintype "passive"))
    )
    (net (code "50") (name "Net-(SW13-Pad3)") (class "Default")
      (node (ref "SW13") (pin "3") (pinfunction "3_3") (pintype "passive"))
      (node (ref "SW9") (pin "4") (pinfunction "4_4") (pintype "passive"))
    )
    (net (code "51") (name "Net-(SW13-Pad4)") (class "Default")
      (node (ref "SW13") (pin "4") (pinfunction "4_4") (pintype "passive"))
      (node (ref "SW17") (pin "3") (pinfunction "3_3") (pintype "passive"))
    )
    (net (code "52") (name "Net-(SW14-Pad4)") (class "Default")
      (node (ref "SW14") (pin "4") (pinfunction "4_4") (pintype "passive"))
      (node (ref "SW18") (pin "3") (pinfunction "3_3") (pintype "passive"))
    )
    (net (code "53") (name "Net-(SW15-Pad4)") (class "Default")
      (node (ref "SW15") (pin "4") (pinfunction "4_4") (pintype "passive"))
      (node (ref "SW19") (pin "3") (pinfunction "3_3") (pintype "passive"))
    )
    (net (code "54") (name "Net-(SW16-Pad4)") (class "Default")
      (node (ref "SW16") (pin "4") (pinfunction "4_4") (pintype "passive"))
      (node (ref "SW20") (pin "3") (pinfunction "3_3") (pintype "passive"))
    )
    (net (code "55") (name "V_in") (class "Default")
      (node (ref "C12") (pin "2") (pinfunction "A_2") (pintype "passive"))
      (node (ref "D1") (pin "3") (pinfunction "C_3") (pintype "passive"))
      (node (ref "JP1") (pin "2") (pinfunction "2_2") (pintype "passive"))
      (node (ref "Q1") (pin "2") (pinfunction "S_2") (pintype "passive"))
      (node (ref "U2") (pin "3") (pinfunction "IN_3") (pintype "power_in"))
    )
    (net (code "56") (name "unconnected-(D1-NC-Pad2)") (class "Default")
      (node (ref "D1") (pin "2") (pinfunction "NC_2") (pintype "passive+no_connect"))
    )
    (net (code "57") (name "unconnected-(SW1-Pad1)") (class "Default")
      (node (ref "SW1") (pin "1") (pinfunction "1_1") (pintype "passive"))
    )
    (net (code "58") (name "unconnected-(SW1-Pad3)") (class "Default")
      (node (ref "SW1") (pin "3") (pinfunction "3_3") (pintype "passive"))
    )
    (net (code "59") (name "unconnected-(SW2-Pad1)") (class "Default")
      (node (ref "SW2") (pin "1") (pinfunction "1_1") (pintype "passive"))
    )
    (net (code "60") (name "unconnected-(SW2-Pad3)") (class "Default")
      (node (ref "SW2") (pin "3") (pinfunction "3_3") (pintype "passive"))
    )
    (net (code "61") (name "unconnected-(SW3-Pad1)") (class "Default")
      (node (ref "SW3") (pin "1") (pinfunction "1_1") (pintype "passive"))
    )
    (net (code "62") (name "unconnected-(SW3-Pad3)") (class "Default")
      (node (ref "SW3") (pin "3") (pinfunction "3_3") (pintype "passive"))
    )
    (net (code "63") (name "unconnected-(SW4-Pad1)") (class "Default")
      (node (ref "SW4") (pin "1") (pinfunction "1_1") (pintype "passive"))
    )
    (net (code "64") (name "unconnected-(SW4-Pad3)") (class "Default")
      (node (ref "SW4") (pin "3") (pinfunction "3_3") (pintype "passive"))
    )
    (net (code "65") (name "unconnected-(SW5-Pad1)") (class "Default")
      (node (ref "SW5") (pin "1") (pinfunction "1_1") (pintype "passive"))
    )
    (net (code "66") (name "unconnected-(SW6-Pad1)") (class "Default")
      (node (ref "SW6") (pin "1") (pinfunction "1_1") (pintype "passive"))
    )
    (net (code "67") (name "unconnected-(SW7-Pad1)") (class "Default")
      (node (ref "SW7") (pin "1") (pinfunction "1_1") (pintype "passive"))
    )
    (net (code "68") (name "unconnected-(SW8-Pad1)") (class "Default")
      (node (ref "SW8") (pin "1") (pinfunction "1_1") (pintype "passive"))
    )
    (net (code "69") (name "unconnected-(SW9-Pad1)") (class "Default")
      (node (ref "SW9") (pin "1") (pinfunction "1_1") (pintype "passive"))
    )
    (net (code "70") (name "unconnected-(SW10-Pad1)") (class "Default")
      (node (ref "SW10") (pin "1") (pinfunction "1_1") (pintype "passive"))
    )
    (net (code "71") (name "unconnected-(SW11-Pad1)") (class "Default")
      (node (ref "SW11") (pin "1") (pinfunction "1_1") (pintype "passive"))
    )
    (net (code "72") (name "unconnected-(SW12-Pad1)") (class "Default")
      (node (ref "SW12") (pin "1") (pinfunction "1_1") (pintype "passive"))
    )
    (net (code "73") (name "unconnected-(SW13-Pad1)") (class "Default")
      (node (ref "SW13") (pin "1") (pinfunction "1_1") (pintype "passive"))
    )
    (net (code "74") (name "unconnected-(SW14-Pad1)") (class "Default")
      (node (ref "SW14") (pin "1") (pinfunction "1_1") (pintype "passive"))
    )
    (net (code "75") (name "unconnected-(SW15-Pad1)") (class "Default")
      (node (ref "SW15") (pin "1") (pinfunction "1_1") (pintype "passive"))
    )
    (net (code "76") (name "unconnected-(SW16-Pad1)") (class "Default")
      (node (ref "SW16") (pin "1") (pinfunction "1_1") (pintype "passive"))
    )
    (net (code "77") (name "unconnected-(SW17-Pad1)") (class "Default")
      (node (ref "SW17") (pin "1") (pinfunction "1_1") (pintype "passive"))
    )
    (net (code "78") (name "unconnected-(SW18-Pad1)") (class "Default")
      (node (ref "SW18") (pin "1") (pinfunction "1_1") (pintype "passive"))
    )
    (net (code "79") (name "unconnected-(SW19-Pad1)") (class "Default")
      (node (ref "SW19") (pin "1") (pinfunction "1_1") (pintype "passive"))
    )
    (net (code "80") (name "unconnected-(SW20-Pad1)") (class "Default")
      (node (ref "SW20") (pin "1") (pinfunction "1_1") (pintype "passive"))
    )
    (net (code "81") (name "unconnected-(U1A-PA1-Pad11)") (class "Default")
      (node (ref "U1") (pin "11") (pinfunction "PA1_11") (pintype "bidirectional+no_connect"))
    )
    (net (code "82") (name "unconnected-(U1A-PA2-Pad12)") (class "Default")
      (node (ref "U1") (pin "12") (pinfunction "PA2_12") (pintype "bidirectional+no_connect"))
    )
    (net (code "83") (name "unconnected-(U1A-PA3-Pad13)") (class "Default")
      (node (ref "U1") (pin "13") (pinfunction "PA3_13") (pintype "bidirectional+no_connect"))
    )
    (net (code "84") (name "unconnected-(U1A-PA9-Pad30)") (class "Default")
      (node (ref "U1") (pin "30") (pinfunction "PA9_30") (pintype "bidirectional+no_connect"))
    )
    (net (code "85") (name "unconnected-(U1A-PA10-Pad31)") (class "Default")
      (node (ref "U1") (pin "31") (pinfunction "PA10_31") (pintype "bidirectional+no_connect"))
    )
    (net (code "86") (name "unconnected-(U1A-PA11-Pad32)") (class "Default")
      (node (ref "U1") (pin "32") (pinfunction "PA11_32") (pintype "bidirectional+no_connect"))
    )
    (net (code "87") (name "unconnected-(U1A-PA12-Pad33)") (class "Default")
      (node (ref "U1") (pin "33") (pinfunction "PA12_33") (pintype "bidirectional+no_connect"))
    )
    (net (code "88") (name "unconnected-(U1A-PA13-Pad34)") (class "Default")
      (node (ref "U1") (pin "34") (pinfunction "PA13_34") (pintype "bidirectional+no_connect"))
    )
    (net (code "89") (name "unconnected-(U1A-PB6-Pad42)") (class "Default")
      (node (ref "U1") (pin "42") (pinfunction "PB6_42") (pintype "bidirectional+no_connect"))
    )
    (net (code "90") (name "unconnected-(U1A-PB7-Pad43)") (class "Default")
      (node (ref "U1") (pin "43") (pinfunction "PB7_43") (pintype "bidirectional+no_connect"))
    )
    (net (code "91") (name "unconnected-(U1A-PB8-Pad45)") (class "Default")
      (node (ref "U1") (pin "45") (pinfunction "PB8_45") (pintype "bidirectional+no_connect"))
    )
    (net (code "92") (name "unconnected-(U1A-PB9-Pad46)") (class "Default")
      (node (ref "U1") (pin "46") (pinfunction "PB9_46") (pintype "bidirectional+no_connect"))
    )
    (net (code "93") (name "unconnected-(U1A-PC13-TAMPER-RTC-Pad2)") (class "Default")
      (node (ref "U1") (pin "2") (pinfunction "PC13-TAMPER-RTC_2") (pintype "bidirectional+no_connect"))
    )
    (net (code "94") (name "unconnected-(U1A-PC14-OSC32_IN-Pad3)") (class "Default")
      (node (ref "U1") (pin "3") (pinfunction "PC14-OSC32_IN_3") (pintype "bidirectional+no_connect"))
    )
    (net (code "95") (name "unconnected-(U1A-PC15-OSC32_OUT-Pad4)") (class "Default")
      (node (ref "U1") (pin "4") (pinfunction "PC15-OSC32_OUT_4") (pintype "bidirectional+no_connect"))
    )
  )
)
